# optMotorDriver.net
KiCad netlist of a schematic drawn in EAGLE
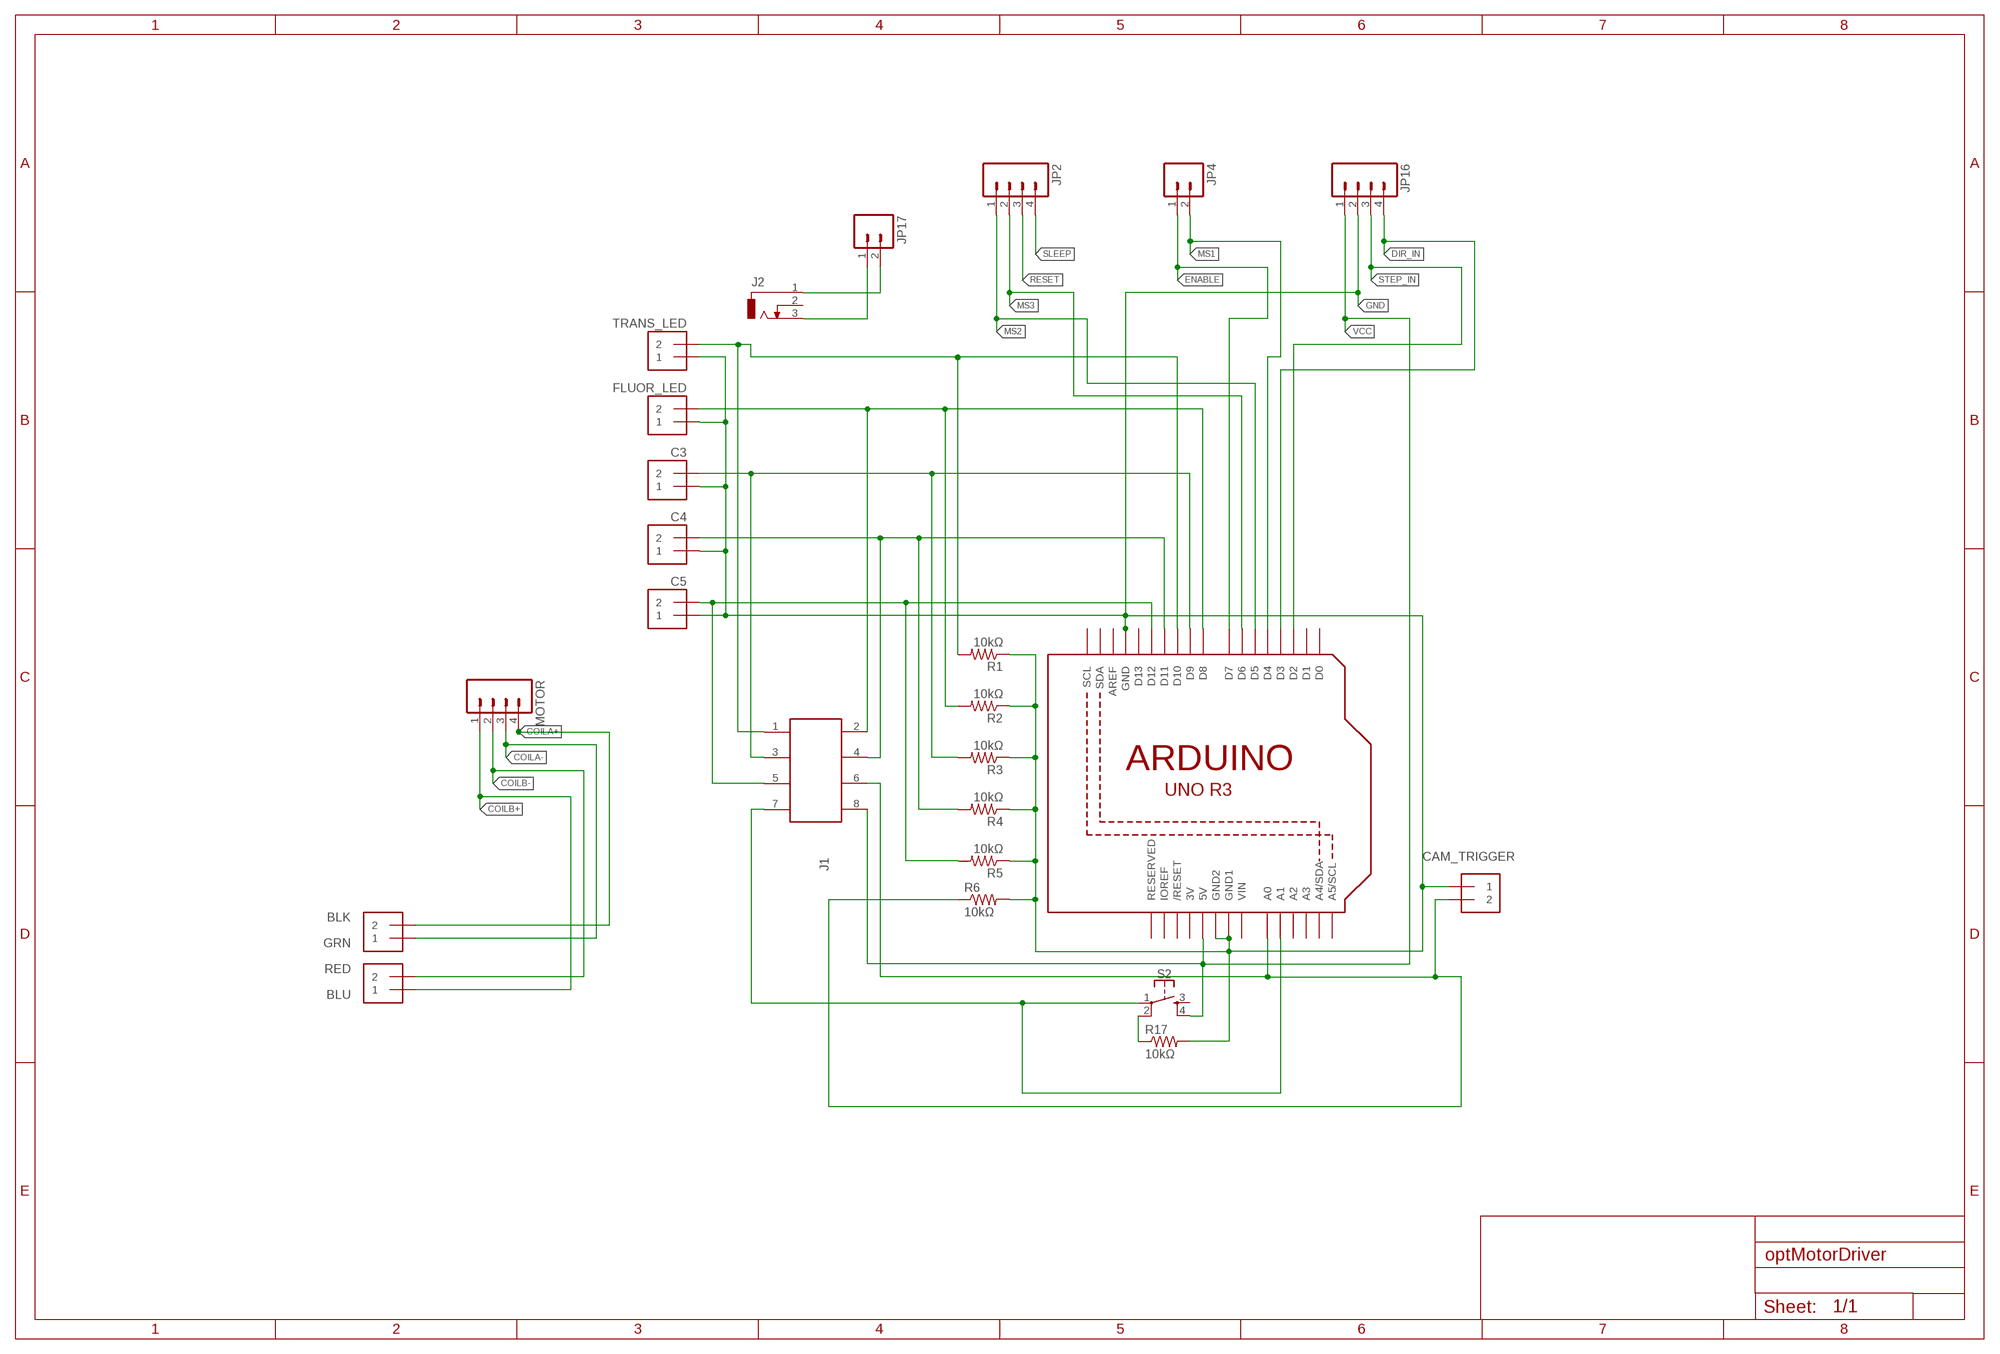
[diagram p0: schematic, sheet 1]

(export (version "E")
  (design (tool "Eeschema 10.0.6"))
  (components
    (comp (ref "ACOIL")
      (value "1X2-3.5MM")
      (footprint "eagle-import:1X2-3.5MM")
      (libsource (lib "eagle-import") (part "1X2-3.5MM"))
    )
    (comp (ref "BCOIL")
      (value "1X2-3.5MM")
      (footprint "eagle-import:1X2-3.5MM")
      (libsource (lib "eagle-import") (part "1X2-3.5MM"))
    )
    (comp (ref "C1")
      (value "1X2-3.5MM")
      (footprint "eagle-import:1X2-3.5MM")
      (libsource (lib "eagle-import") (part "1X2-3.5MM"))
    )
    (comp (ref "C2")
      (value "1X2-3.5MM")
      (footprint "eagle-import:1X2-3.5MM")
      (libsource (lib "eagle-import") (part "1X2-3.5MM"))
    )
    (comp (ref "C3")
      (value "1X2-3.5MM")
      (footprint "eagle-import:1X2-3.5MM")
      (libsource (lib "eagle-import") (part "1X2-3.5MM"))
    )
    (comp (ref "C4")
      (value "1X2-3.5MM")
      (footprint "eagle-import:1X2-3.5MM")
      (libsource (lib "eagle-import") (part "1X2-3.5MM"))
    )
    (comp (ref "C5")
      (value "1X2-3.5MM")
      (footprint "eagle-import:1X2-3.5MM")
      (libsource (lib "eagle-import") (part "1X2-3.5MM"))
    )
    (comp (ref "J1")
      (value "62400821722")
      (footprint "eagle-import:62400821722")
      (libsource (lib "eagle-import") (part "62400821722"))
    )
    (comp (ref "J2")
      (value "DCJ0303")
      (footprint "eagle-import:DCJ0303")
      (libsource (lib "eagle-import") (part "DCJ0303"))
    )
    (comp (ref "JP2")
      (value "M04PTH")
      (footprint "eagle-import:1X04")
      (libsource (lib "eagle-import") (part "M04PTH"))
    )
    (comp (ref "JP4")
      (value "M02PTH")
      (footprint "eagle-import:1X02")
      (libsource (lib "eagle-import") (part "M02PTH"))
    )
    (comp (ref "JP16")
      (value "M04PTH")
      (footprint "eagle-import:1X04")
      (libsource (lib "eagle-import") (part "M04PTH"))
    )
    (comp (ref "JP17")
      (value "M02PTH")
      (footprint "eagle-import:1X02")
      (libsource (lib "eagle-import") (part "M02PTH"))
    )
    (comp (ref "MOTOR")
      (value "M04PTH")
      (footprint "eagle-import:1X04")
      (libsource (lib "eagle-import") (part "M04PTH"))
    )
    (comp (ref "R1")
      (value "10kΩ")
      (footprint "eagle-import:R1206")
      (libsource (lib "eagle-import") (part "R-US_R1206"))
    )
    (comp (ref "R2")
      (value "10kΩ")
      (footprint "eagle-import:R1206")
      (libsource (lib "eagle-import") (part "R-US_R1206"))
    )
    (comp (ref "R3")
      (value "10kΩ")
      (footprint "eagle-import:R1206")
      (libsource (lib "eagle-import") (part "R-US_R1206"))
    )
    (comp (ref "R4")
      (value "10kΩ")
      (footprint "eagle-import:R1206")
      (libsource (lib "eagle-import") (part "R-US_R1206"))
    )
    (comp (ref "R5")
      (value "10kΩ")
      (footprint "eagle-import:R1206")
      (libsource (lib "eagle-import") (part "R-US_R1206"))
    )
    (comp (ref "R6")
      (value "10kΩ")
      (footprint "eagle-import:R1206")
      (libsource (lib "eagle-import") (part "R-US_R1206"))
    )
    (comp (ref "R17")
      (value "10kΩ")
      (footprint "eagle-import:R1206")
      (libsource (lib "eagle-import") (part "R-US_R1206"))
    )
    (comp (ref "S2")
      (value "MOMENTARY-SWITCH-SPST-2-SMD-5.2MM")
      (footprint "eagle-import:TACTILE_SWITCH_SMD_5.2MM")
      (libsource (lib "eagle-import") (part "MOMENTARY-SWITCH-SPST-2-SMD-5.2MM"))
    )
    (comp (ref "TRIGGER")
      (value "1X2-3.5MM")
      (footprint "eagle-import:1X2-3.5MM")
      (libsource (lib "eagle-import") (part "1X2-3.5MM"))
    )
    (comp (ref "U1")
      (value "ARDUINOR3-DIMENSION")
      (footprint "eagle-import:ARDUINOR3")
      (libsource (lib "eagle-import") (part "ARDUINOR3-DIMENSION"))
    )
  )
  (nets
    (net (code "1") (name "/3V") (class "Default")
      (node (ref "U1") (pin "3V") (pinfunction "3V_3V") (pintype "power_in"))
    )
    (net (code "2") (name "/VIN") (class "Default")
      (node (ref "U1") (pin "VIN") (pinfunction "VIN_VIN") (pintype "power_in"))
    )
    (net (code "3") (name "COILA+") (class "Default")
      (node (ref "ACOIL") (pin "2") (pinfunction "2_2") (pintype "passive"))
      (node (ref "MOTOR") (pin "4") (pinfunction "4_4") (pintype "passive"))
    )
    (net (code "4") (name "COILA-") (class "Default")
      (node (ref "ACOIL") (pin "1") (pinfunction "1_1") (pintype "passive"))
      (node (ref "MOTOR") (pin "3") (pinfunction "3_3") (pintype "passive"))
    )
    (net (code "5") (name "COILB+") (class "Default")
      (node (ref "BCOIL") (pin "1") (pinfunction "1_1") (pintype "passive"))
      (node (ref "MOTOR") (pin "1") (pinfunction "1_1") (pintype "passive"))
    )
    (net (code "6") (name "COILB-") (class "Default")
      (node (ref "BCOIL") (pin "2") (pinfunction "2_2") (pintype "passive"))
      (node (ref "MOTOR") (pin "2") (pinfunction "2_2") (pintype "passive"))
    )
    (net (code "7") (name "DIR_IN") (class "Default")
      (node (ref "JP16") (pin "4") (pinfunction "4_4") (pintype "passive"))
      (node (ref "U1") (pin "D3") (pinfunction "D3_D3") (pintype "bidirectional"))
    )
    (net (code "8") (name "ENABLE") (class "Default")
      (node (ref "JP4") (pin "1") (pinfunction "1_1") (pintype "passive"))
      (node (ref "U1") (pin "D7") (pinfunction "D7_D7") (pintype "bidirectional"))
    )
    (net (code "9") (name "GND") (class "Default")
      (node (ref "C1") (pin "1") (pinfunction "1_1") (pintype "passive"))
      (node (ref "C2") (pin "1") (pinfunction "1_1") (pintype "passive"))
      (node (ref "C3") (pin "1") (pinfunction "1_1") (pintype "passive"))
      (node (ref "C4") (pin "1") (pinfunction "1_1") (pintype "passive"))
      (node (ref "C5") (pin "1") (pinfunction "1_1") (pintype "passive"))
      (node (ref "JP16") (pin "2") (pinfunction "2_2") (pintype "passive"))
      (node (ref "R1") (pin "1") (pinfunction "1_1") (pintype "passive"))
      (node (ref "R17") (pin "2") (pinfunction "2_2") (pintype "passive"))
      (node (ref "R2") (pin "1") (pinfunction "1_1") (pintype "passive"))
      (node (ref "R3") (pin "1") (pinfunction "1_1") (pintype "passive"))
      (node (ref "R4") (pin "1") (pinfunction "1_1") (pintype "passive"))
      (node (ref "R5") (pin "1") (pinfunction "1_1") (pintype "passive"))
      (node (ref "R6") (pin "2") (pinfunction "2_2") (pintype "passive"))
      (node (ref "TRIGGER") (pin "1") (pinfunction "1_1") (pintype "passive"))
      (node (ref "U1") (pin "GND") (pinfunction "GND_GND") (pintype "power_in"))
      (node (ref "U1") (pin "GND1") (pinfunction "GND1_GND1") (pintype "power_in"))
      (node (ref "U1") (pin "GND2") (pinfunction "GND2_GND2") (pintype "power_in"))
    )
    (net (code "10") (name "MS1") (class "Default")
      (node (ref "JP4") (pin "2") (pinfunction "2_2") (pintype "passive"))
      (node (ref "U1") (pin "D4") (pinfunction "D4_D4") (pintype "bidirectional"))
    )
    (net (code "11") (name "MS2") (class "Default")
      (node (ref "JP2") (pin "1") (pinfunction "1_1") (pintype "passive"))
      (node (ref "U1") (pin "D5") (pinfunction "D5_D5") (pintype "bidirectional"))
    )
    (net (code "12") (name "MS3") (class "Default")
      (node (ref "JP2") (pin "2") (pinfunction "2_2") (pintype "passive"))
      (node (ref "U1") (pin "D6") (pinfunction "D6_D6") (pintype "bidirectional"))
    )
    (net (code "13") (name "Net-(J1-1)") (class "Default")
      (node (ref "J1") (pin "7") (pinfunction "1_7") (pintype "passive"))
      (node (ref "S2") (pin "1") (pinfunction "1_1") (pintype "passive"))
      (node (ref "U1") (pin "A1") (pinfunction "A1_A1") (pintype "bidirectional"))
    )
    (net (code "14") (name "Net-(J1-3)") (class "Default")
      (node (ref "C5") (pin "2") (pinfunction "2_2") (pintype "passive"))
      (node (ref "J1") (pin "5") (pinfunction "3_5") (pintype "passive"))
      (node (ref "R5") (pin "2") (pinfunction "2_2") (pintype "passive"))
      (node (ref "U1") (pin "D12") (pinfunction "D12_D12") (pintype "bidirectional"))
    )
    (net (code "15") (name "Net-(J1-4)") (class "Default")
      (node (ref "J1") (pin "6") (pinfunction "4_6") (pintype "passive"))
      (node (ref "R6") (pin "1") (pinfunction "1_1") (pintype "passive"))
      (node (ref "TRIGGER") (pin "2") (pinfunction "2_2") (pintype "passive"))
      (node (ref "U1") (pin "A0") (pinfunction "A0_A0") (pintype "bidirectional"))
    )
    (net (code "16") (name "Net-(J1-5)") (class "Default")
      (node (ref "C3") (pin "2") (pinfunction "2_2") (pintype "passive"))
      (node (ref "J1") (pin "3") (pinfunction "5_3") (pintype "passive"))
      (node (ref "R3") (pin "2") (pinfunction "2_2") (pintype "passive"))
      (node (ref "U1") (pin "D9") (pinfunction "D9_D9") (pintype "bidirectional"))
    )
    (net (code "17") (name "Net-(J1-6)") (class "Default")
      (node (ref "C4") (pin "2") (pinfunction "2_2") (pintype "passive"))
      (node (ref "J1") (pin "4") (pinfunction "6_4") (pintype "passive"))
      (node (ref "R4") (pin "2") (pinfunction "2_2") (pintype "passive"))
      (node (ref "U1") (pin "D11") (pinfunction "D11_D11") (pintype "bidirectional"))
    )
    (net (code "18") (name "Net-(J1-7)") (class "Default")
      (node (ref "C1") (pin "2") (pinfunction "2_2") (pintype "passive"))
      (node (ref "J1") (pin "1") (pinfunction "7_1") (pintype "passive"))
      (node (ref "R1") (pin "2") (pinfunction "2_2") (pintype "passive"))
      (node (ref "U1") (pin "D10") (pinfunction "D10_D10") (pintype "bidirectional"))
    )
    (net (code "19") (name "Net-(J1-8)") (class "Default")
      (node (ref "C2") (pin "2") (pinfunction "2_2") (pintype "passive"))
      (node (ref "J1") (pin "2") (pinfunction "8_2") (pintype "passive"))
      (node (ref "R2") (pin "2") (pinfunction "2_2") (pintype "passive"))
      (node (ref "U1") (pin "D8") (pinfunction "D8_D8") (pintype "bidirectional"))
    )
    (net (code "20") (name "Net-(J2-Pad1)") (class "Default")
      (node (ref "J2") (pin "1") (pinfunction "1_1") (pintype "passive"))
      (node (ref "JP17") (pin "2") (pinfunction "2_2") (pintype "passive"))
    )
    (net (code "21") (name "Net-(J2-Pad3)") (class "Default")
      (node (ref "J2") (pin "3") (pinfunction "3_3") (pintype "passive"))
      (node (ref "JP17") (pin "1") (pinfunction "1_1") (pintype "passive"))
    )
    (net (code "22") (name "Net-(R17-Pad1)") (class "Default")
      (node (ref "R17") (pin "1") (pinfunction "1_1") (pintype "passive"))
      (node (ref "S2") (pin "2") (pinfunction "2_2") (pintype "passive"))
    )
    (net (code "23") (name "RESET") (class "Default")
      (node (ref "JP2") (pin "3") (pinfunction "3_3") (pintype "passive"))
    )
    (net (code "24") (name "SLEEP") (class "Default")
      (node (ref "JP2") (pin "4") (pinfunction "4_4") (pintype "passive"))
    )
    (net (code "25") (name "STEP_IN") (class "Default")
      (node (ref "JP16") (pin "3") (pinfunction "3_3") (pintype "passive"))
      (node (ref "U1") (pin "D2") (pinfunction "D2_D2") (pintype "bidirectional"))
    )
    (net (code "26") (name "VCC") (class "Default")
      (node (ref "J1") (pin "8") (pinfunction "2_8") (pintype "passive"))
      (node (ref "JP16") (pin "1") (pinfunction "1_1") (pintype "passive"))
      (node (ref "S2") (pin "4") (pinfunction "4_4") (pintype "passive"))
      (node (ref "U1") (pin "5V") (pinfunction "5V_5V") (pintype "power_in"))
    )
    (net (code "27") (name "unconnected-(J2-Pad2)") (class "Default")
      (node (ref "J2") (pin "2") (pinfunction "2_2") (pintype "passive"))
    )
    (net (code "28") (name "unconnected-(S2-Pad3)") (class "Default")
      (node (ref "S2") (pin "3") (pinfunction "3_3") (pintype "passive"))
    )
    (net (code "29") (name "unconnected-(U1-A4{slash}SDA-PadA4)") (class "Default")
      (node (ref "U1") (pin "A4") (pinfunction "A4/SDA_A4") (pintype "bidirectional"))
    )
    (net (code "30") (name "unconnected-(U1-A5{slash}SCL-PadA5)") (class "Default")
      (node (ref "U1") (pin "A5") (pinfunction "A5/SCL_A5") (pintype "bidirectional"))
    )
    (net (code "31") (name "unconnected-(U1-PadA2)") (class "Default")
      (node (ref "U1") (pin "A2") (pinfunction "A2_A2") (pintype "bidirectional"))
    )
    (net (code "32") (name "unconnected-(U1-PadA3)") (class "Default")
      (node (ref "U1") (pin "A3") (pinfunction "A3_A3") (pintype "bidirectional"))
    )
    (net (code "33") (name "unconnected-(U1-PadAREF)") (class "Default")
      (node (ref "U1") (pin "AREF") (pinfunction "AREF_AREF") (pintype "bidirectional"))
    )
    (net (code "34") (name "unconnected-(U1-PadD0)") (class "Default")
      (node (ref "U1") (pin "D0") (pinfunction "D0_D0") (pintype "bidirectional"))
    )
    (net (code "35") (name "unconnected-(U1-PadD1)") (class "Default")
      (node (ref "U1") (pin "D1") (pinfunction "D1_D1") (pintype "bidirectional"))
    )
    (net (code "36") (name "unconnected-(U1-PadD13)") (class "Default")
      (node (ref "U1") (pin "D13") (pinfunction "D13_D13") (pintype "bidirectional"))
    )
    (net (code "37") (name "unconnected-(U1-PadIOREF)") (class "Default")
      (node (ref "U1") (pin "IOREF") (pinfunction "IOREF_IOREF") (pintype "output"))
    )
    (net (code "38") (name "unconnected-(U1-PadRESERVED)") (class "Default")
      (node (ref "U1") (pin "RESERVED") (pinfunction "RESERVED_RESERVED") (pintype "no_connect"))
    )
    (net (code "39") (name "unconnected-(U1-PadSCL)") (class "Default")
      (node (ref "U1") (pin "SCL") (pinfunction "SCL_SCL") (pintype "bidirectional"))
    )
    (net (code "40") (name "unconnected-(U1-PadSDA)") (class "Default")
      (node (ref "U1") (pin "SDA") (pinfunction "SDA_SDA") (pintype "bidirectional"))
    )
    (net (code "41") (name "unconnected-(U1-{slash}RESET-PadRESET)") (class "Default")
      (node (ref "U1") (pin "RESET") (pinfunction "/RESET_RESET") (pintype "bidirectional"))
    )
  )
)
